# SCH_XO-PAD_2026-07-20.net
KiCad netlist of a schematic drawn in EasyEDA
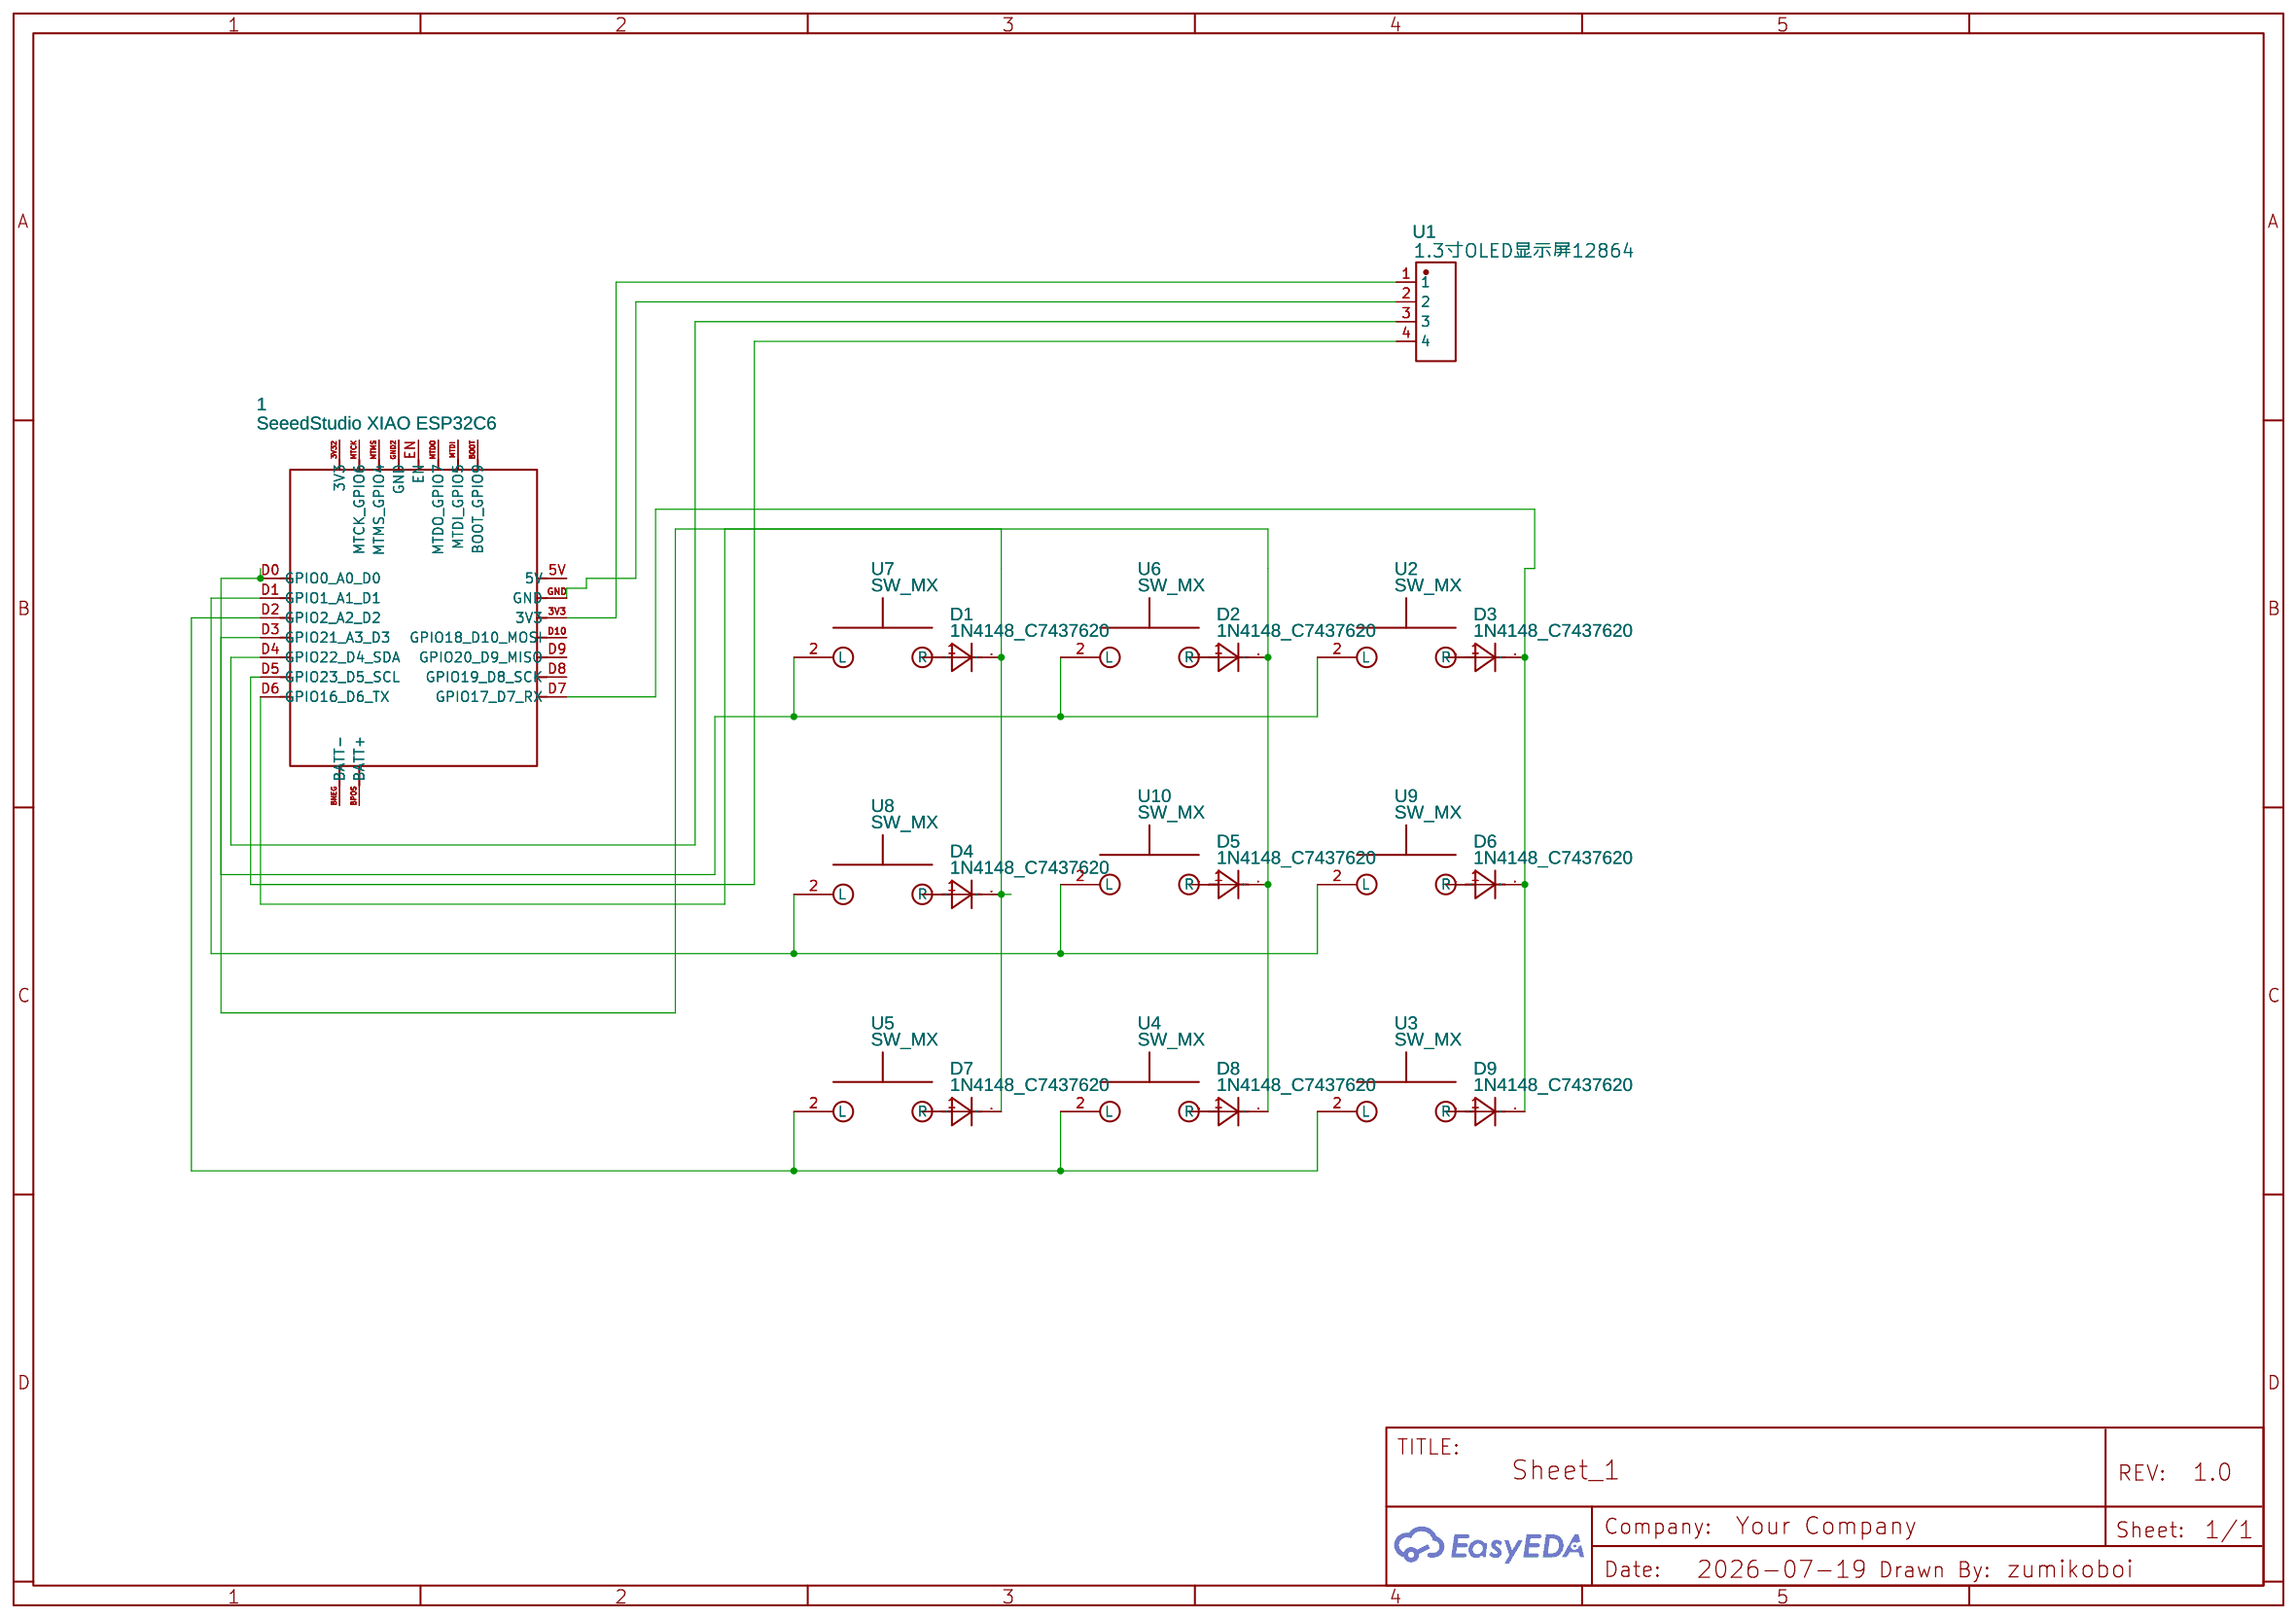
[diagram p0: schematic sheet]

(export (version "E")
  (design (tool "Eeschema 10.0.6"))
  (components
    (comp (ref "1") (value "SeeedStudio XIAO ESP32C6") (libsource (lib "") (part "SeeedStudio XIAO ESP32C6")))
    (comp (ref "D1")
      (value "1N4148_C7437620")
      (fields (field (name "Manufacturer Part") "1N4148") (field (name "Manufacturer") "XCH(旭昌辉)"))
      (libsource (lib "") (part "1N4148_C7437620"))
    )
    (comp (ref "D2")
      (value "1N4148_C7437620")
      (fields (field (name "Manufacturer Part") "1N4148") (field (name "Manufacturer") "XCH(旭昌辉)"))
      (libsource (lib "") (part "1N4148_C7437620"))
    )
    (comp (ref "D3")
      (value "1N4148_C7437620")
      (fields (field (name "Manufacturer Part") "1N4148") (field (name "Manufacturer") "XCH(旭昌辉)"))
      (libsource (lib "") (part "1N4148_C7437620"))
    )
    (comp (ref "D4")
      (value "1N4148_C7437620")
      (fields (field (name "Manufacturer Part") "1N4148") (field (name "Manufacturer") "XCH(旭昌辉)"))
      (libsource (lib "") (part "1N4148_C7437620"))
    )
    (comp (ref "D5")
      (value "1N4148_C7437620")
      (fields (field (name "Manufacturer Part") "1N4148") (field (name "Manufacturer") "XCH(旭昌辉)"))
      (libsource (lib "") (part "1N4148_C7437620"))
    )
    (comp (ref "D6")
      (value "1N4148_C7437620")
      (fields (field (name "Manufacturer Part") "1N4148") (field (name "Manufacturer") "XCH(旭昌辉)"))
      (libsource (lib "") (part "1N4148_C7437620"))
    )
    (comp (ref "D7")
      (value "1N4148_C7437620")
      (fields (field (name "Manufacturer Part") "1N4148") (field (name "Manufacturer") "XCH(旭昌辉)"))
      (libsource (lib "") (part "1N4148_C7437620"))
    )
    (comp (ref "D8")
      (value "1N4148_C7437620")
      (fields (field (name "Manufacturer Part") "1N4148") (field (name "Manufacturer") "XCH(旭昌辉)"))
      (libsource (lib "") (part "1N4148_C7437620"))
    )
    (comp (ref "D9")
      (value "1N4148_C7437620")
      (fields (field (name "Manufacturer Part") "1N4148") (field (name "Manufacturer") "XCH(旭昌辉)"))
      (libsource (lib "") (part "1N4148_C7437620"))
    )
    (comp (ref "U1") (value "1.3寸OLED显示屏12864") (libsource (lib "") (part "1.3寸OLED显示屏12864")))
    (comp (ref "U2") (value "SW_MX") (libsource (lib "") (part "SW_MX")))
    (comp (ref "U3") (value "SW_MX") (libsource (lib "") (part "SW_MX")))
    (comp (ref "U4") (value "SW_MX") (libsource (lib "") (part "SW_MX")))
    (comp (ref "U5") (value "SW_MX") (libsource (lib "") (part "SW_MX")))
    (comp (ref "U6") (value "SW_MX") (libsource (lib "") (part "SW_MX")))
    (comp (ref "U7") (value "SW_MX") (libsource (lib "") (part "SW_MX")))
    (comp (ref "U8") (value "SW_MX") (libsource (lib "") (part "SW_MX")))
    (comp (ref "U9") (value "SW_MX") (libsource (lib "") (part "SW_MX")))
    (comp (ref "U10") (value "SW_MX") (libsource (lib "") (part "SW_MX")))
  )
  (nets
    (net (code "1") (name "Net-(1-GPIO0_A0_D0)") (class "Default")
      (node (ref "1") (pin "D0") (pinfunction "GPIO0_A0_D0_D0") (pintype "bidirectional"))
      (node (ref "U2") (pin "2") (pinfunction "L_2") (pintype "unspecified"))
      (node (ref "U6") (pin "2") (pinfunction "L_2") (pintype "unspecified"))
      (node (ref "U7") (pin "2") (pinfunction "L_2") (pintype "unspecified"))
    )
    (net (code "2") (name "Net-(1-GPIO1_A1_D1)") (class "Default")
      (node (ref "1") (pin "D1") (pinfunction "GPIO1_A1_D1_D1") (pintype "bidirectional"))
      (node (ref "U10") (pin "2") (pinfunction "L_2") (pintype "unspecified"))
      (node (ref "U8") (pin "2") (pinfunction "L_2") (pintype "unspecified"))
      (node (ref "U9") (pin "2") (pinfunction "L_2") (pintype "unspecified"))
    )
    (net (code "3") (name "Net-(1-GPIO2_A2_D2)") (class "Default")
      (node (ref "1") (pin "D2") (pinfunction "GPIO2_A2_D2_D2") (pintype "bidirectional"))
      (node (ref "U3") (pin "2") (pinfunction "L_2") (pintype "unspecified"))
      (node (ref "U4") (pin "2") (pinfunction "L_2") (pintype "unspecified"))
      (node (ref "U5") (pin "2") (pinfunction "L_2") (pintype "unspecified"))
    )
    (net (code "4") (name "Net-(1-GPIO16_D6_TX)") (class "Default")
      (node (ref "1") (pin "D6") (pinfunction "GPIO16_D6_TX_D6") (pintype "bidirectional"))
      (node (ref "D2") (pin "2") (pinfunction "C_2") (pintype "unspecified"))
      (node (ref "D5") (pin "2") (pinfunction "C_2") (pintype "unspecified"))
      (node (ref "D8") (pin "2") (pinfunction "C_2") (pintype "unspecified"))
    )
    (net (code "5") (name "Net-(1-GPIO17_D7_RX)") (class "Default")
      (node (ref "1") (pin "D7") (pinfunction "GPIO17_D7_RX_D7") (pintype "bidirectional"))
      (node (ref "D3") (pin "2") (pinfunction "C_2") (pintype "unspecified"))
      (node (ref "D6") (pin "2") (pinfunction "C_2") (pintype "unspecified"))
      (node (ref "D9") (pin "2") (pinfunction "C_2") (pintype "unspecified"))
    )
    (net (code "6") (name "Net-(1-GPIO21_A3_D3)") (class "Default")
      (node (ref "1") (pin "D3") (pinfunction "GPIO21_A3_D3_D3") (pintype "bidirectional"))
      (node (ref "D1") (pin "2") (pinfunction "C_2") (pintype "unspecified"))
      (node (ref "D4") (pin "2") (pinfunction "C_2") (pintype "unspecified"))
      (node (ref "D7") (pin "2") (pinfunction "C_2") (pintype "unspecified"))
    )
    (net (code "7") (name "Net-(1-GPIO22_D4_SDA)") (class "Default")
      (node (ref "1") (pin "D4") (pinfunction "GPIO22_D4_SDA_D4") (pintype "bidirectional"))
      (node (ref "U1") (pin "3") (pinfunction "3_3") (pintype "unspecified"))
    )
    (net (code "8") (name "Net-(1-GPIO23_D5_SCL)") (class "Default")
      (node (ref "1") (pin "D5") (pinfunction "GPIO23_D5_SCL_D5") (pintype "bidirectional"))
      (node (ref "U1") (pin "4") (pinfunction "4_4") (pintype "unspecified"))
    )
    (net (code "9") (name "Net-(1-Pad3V3)") (class "Default")
      (node (ref "1") (pin "3V3") (pinfunction "3V3_3V3") (pintype "bidirectional"))
      (node (ref "U1") (pin "1") (pinfunction "1_1") (pintype "unspecified"))
    )
    (net (code "10") (name "Net-(1-PadGND)") (class "Default")
      (node (ref "1") (pin "GND") (pinfunction "GND_GND") (pintype "bidirectional"))
      (node (ref "U1") (pin "2") (pinfunction "2_2") (pintype "unspecified"))
    )
    (net (code "11") (name "unconnected-(1-3V3-Pad3V32)") (class "Default")
      (node (ref "1") (pin "3V32") (pinfunction "3V3_3V32") (pintype "bidirectional"))
    )
    (net (code "12") (name "unconnected-(1-BATT+-PadBPOS)") (class "Default")
      (node (ref "1") (pin "BPOS") (pinfunction "BATT+_BPOS") (pintype "bidirectional"))
    )
    (net (code "13") (name "unconnected-(1-BATT--PadBNEG)") (class "Default")
      (node (ref "1") (pin "BNEG") (pinfunction "BATT-_BNEG") (pintype "bidirectional"))
    )
    (net (code "14") (name "unconnected-(1-BOOT_GPIO9-PadBOOT)") (class "Default")
      (node (ref "1") (pin "BOOT") (pinfunction "BOOT_GPIO9_BOOT") (pintype "bidirectional"))
    )
    (net (code "15") (name "unconnected-(1-GND-PadGND2)") (class "Default")
      (node (ref "1") (pin "GND2") (pinfunction "GND_GND2") (pintype "bidirectional"))
    )
    (net (code "16") (name "unconnected-(1-GPIO18_D10_MOSI-PadD10)") (class "Default")
      (node (ref "1") (pin "D10") (pinfunction "GPIO18_D10_MOSI_D10") (pintype "bidirectional"))
    )
    (net (code "17") (name "unconnected-(1-GPIO19_D8_SCK-PadD8)") (class "Default")
      (node (ref "1") (pin "D8") (pinfunction "GPIO19_D8_SCK_D8") (pintype "bidirectional"))
    )
    (net (code "18") (name "unconnected-(1-GPIO20_D9_MISO-PadD9)") (class "Default")
      (node (ref "1") (pin "D9") (pinfunction "GPIO20_D9_MISO_D9") (pintype "bidirectional"))
    )
    (net (code "19") (name "unconnected-(1-MTCK_GPIO6-PadMTCK)") (class "Default")
      (node (ref "1") (pin "MTCK") (pinfunction "MTCK_GPIO6_MTCK") (pintype "bidirectional"))
    )
    (net (code "20") (name "unconnected-(1-MTDI_GPIO5-PadMTDI)") (class "Default")
      (node (ref "1") (pin "MTDI") (pinfunction "MTDI_GPIO5_MTDI") (pintype "bidirectional"))
    )
    (net (code "21") (name "unconnected-(1-MTDO_GPIO7-PadMTDO)") (class "Default")
      (node (ref "1") (pin "MTDO") (pinfunction "MTDO_GPIO7_MTDO") (pintype "bidirectional"))
    )
    (net (code "22") (name "unconnected-(1-MTMS_GPIO4-PadMTMS)") (class "Default")
      (node (ref "1") (pin "MTMS") (pinfunction "MTMS_GPIO4_MTMS") (pintype "bidirectional"))
    )
    (net (code "23") (name "unconnected-(1-Pad5V)") (class "Default")
      (node (ref "1") (pin "5V") (pinfunction "5V_5V") (pintype "bidirectional"))
    )
    (net (code "24") (name "unconnected-(1-PadEN)") (class "Default")
      (node (ref "1") (pin "EN") (pinfunction "EN_EN") (pintype "bidirectional"))
    )
    (net (code "25") (name "unconnected-(D1-A-Pad1)") (class "Default")
      (node (ref "D1") (pin "1") (pinfunction "A_1") (pintype "unspecified"))
    )
    (net (code "26") (name "unconnected-(D2-A-Pad1)") (class "Default")
      (node (ref "D2") (pin "1") (pinfunction "A_1") (pintype "unspecified"))
    )
    (net (code "27") (name "unconnected-(D3-A-Pad1)") (class "Default")
      (node (ref "D3") (pin "1") (pinfunction "A_1") (pintype "unspecified"))
    )
    (net (code "28") (name "unconnected-(D4-A-Pad1)") (class "Default")
      (node (ref "D4") (pin "1") (pinfunction "A_1") (pintype "unspecified"))
    )
    (net (code "29") (name "unconnected-(D5-A-Pad1)") (class "Default")
      (node (ref "D5") (pin "1") (pinfunction "A_1") (pintype "unspecified"))
    )
    (net (code "30") (name "unconnected-(D6-A-Pad1)") (class "Default")
      (node (ref "D6") (pin "1") (pinfunction "A_1") (pintype "unspecified"))
    )
    (net (code "31") (name "unconnected-(D7-A-Pad1)") (class "Default")
      (node (ref "D7") (pin "1") (pinfunction "A_1") (pintype "unspecified"))
    )
    (net (code "32") (name "unconnected-(D8-A-Pad1)") (class "Default")
      (node (ref "D8") (pin "1") (pinfunction "A_1") (pintype "unspecified"))
    )
    (net (code "33") (name "unconnected-(D9-A-Pad1)") (class "Default")
      (node (ref "D9") (pin "1") (pinfunction "A_1") (pintype "unspecified"))
    )
    (net (code "34") (name "unconnected-(U2-R-Pad1)") (class "Default")
      (node (ref "U2") (pin "1") (pinfunction "R_1") (pintype "unspecified"))
    )
    (net (code "35") (name "unconnected-(U3-R-Pad1)") (class "Default")
      (node (ref "U3") (pin "1") (pinfunction "R_1") (pintype "unspecified"))
    )
    (net (code "36") (name "unconnected-(U4-R-Pad1)") (class "Default")
      (node (ref "U4") (pin "1") (pinfunction "R_1") (pintype "unspecified"))
    )
    (net (code "37") (name "unconnected-(U5-R-Pad1)") (class "Default")
      (node (ref "U5") (pin "1") (pinfunction "R_1") (pintype "unspecified"))
    )
    (net (code "38") (name "unconnected-(U6-R-Pad1)") (class "Default")
      (node (ref "U6") (pin "1") (pinfunction "R_1") (pintype "unspecified"))
    )
    (net (code "39") (name "unconnected-(U7-R-Pad1)") (class "Default")
      (node (ref "U7") (pin "1") (pinfunction "R_1") (pintype "unspecified"))
    )
    (net (code "40") (name "unconnected-(U8-R-Pad1)") (class "Default")
      (node (ref "U8") (pin "1") (pinfunction "R_1") (pintype "unspecified"))
    )
    (net (code "41") (name "unconnected-(U9-R-Pad1)") (class "Default")
      (node (ref "U9") (pin "1") (pinfunction "R_1") (pintype "unspecified"))
    )
    (net (code "42") (name "unconnected-(U10-R-Pad1)") (class "Default")
      (node (ref "U10") (pin "1") (pinfunction "R_1") (pintype "unspecified"))
    )
  )
)
